# LED.net
KiCad netlist of a schematic drawn in EAGLE
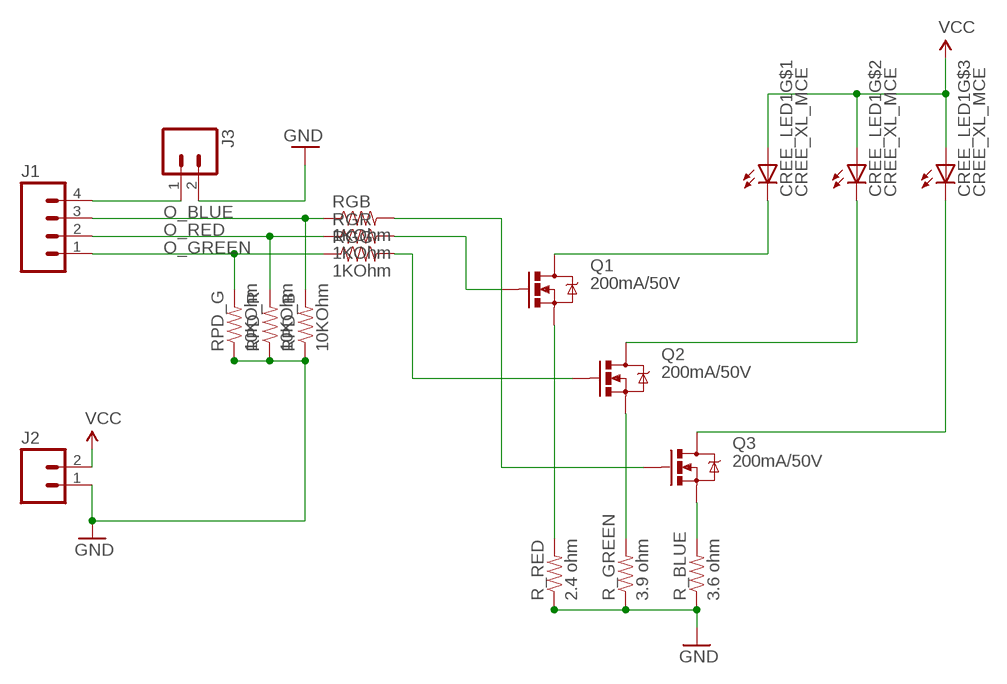
[diagram p0: schematic, sheet 1]

(export (version "E")
  (design (tool "Eeschema 10.0.6"))
  (components
    (comp (ref "CREE_LED1")
      (value "CREE_XL_MCE")
      (footprint "eagle-import:CREE_XL_MCE")
      (libsource (lib "eagle-import") (part "CREE_XL_MCE"))
    )
    (comp (ref "J1")
      (value "M04NO_SILK_ALL_ROUND")
      (footprint "eagle-import:1X04_NO_SILK_ALL_ROUND")
      (libsource (lib "eagle-import") (part "M04NO_SILK_ALL_ROUND"))
    )
    (comp (ref "J2")
      (value "M021X02_NO_SILK")
      (footprint "eagle-import:1X02_NO_SILK")
      (libsource (lib "eagle-import") (part "M021X02_NO_SILK"))
    )
    (comp (ref "J3")
      (value "M021X02_NO_SILK")
      (footprint "eagle-import:1X02_NO_SILK")
      (libsource (lib "eagle-import") (part "M021X02_NO_SILK"))
    )
    (comp (ref "Q1")
      (value "200mA/50V")
      (footprint "eagle-import:SOT23-3")
      (libsource (lib "eagle-import") (part "MOSFET-NCHANNELBSS138"))
    )
    (comp (ref "Q2")
      (value "200mA/50V")
      (footprint "eagle-import:SOT23-3")
      (libsource (lib "eagle-import") (part "MOSFET-NCHANNELBSS138"))
    )
    (comp (ref "Q3")
      (value "200mA/50V")
      (footprint "eagle-import:SOT23-3")
      (libsource (lib "eagle-import") (part "MOSFET-NCHANNELBSS138"))
    )
    (comp (ref "RGB")
      (value "1KOhm")
      (footprint "eagle-import:0805")
      (libsource (lib "eagle-import") (part "RESISTOR0805-RES"))
    )
    (comp (ref "RGG")
      (value "1KOhm")
      (footprint "eagle-import:0805")
      (libsource (lib "eagle-import") (part "RESISTOR0805-RES"))
    )
    (comp (ref "RGR")
      (value "1KOhm")
      (footprint "eagle-import:0805")
      (libsource (lib "eagle-import") (part "RESISTOR0805-RES"))
    )
    (comp (ref "RPD_B")
      (value "10KOhm")
      (footprint "eagle-import:0805")
      (libsource (lib "eagle-import") (part "RESISTOR0805-RES"))
    )
    (comp (ref "RPD_G")
      (value "10KOhm")
      (footprint "eagle-import:0805")
      (libsource (lib "eagle-import") (part "RESISTOR0805-RES"))
    )
    (comp (ref "RPD_R")
      (value "10KOhm")
      (footprint "eagle-import:0805")
      (libsource (lib "eagle-import") (part "RESISTOR0805-RES"))
    )
    (comp (ref "R_BLUE")
      (value "3.6 ohm")
      (footprint "eagle-import:0805")
      (libsource (lib "eagle-import") (part "RESISTOR0805-RES"))
    )
    (comp (ref "R_GREEN")
      (value "3.9 ohm")
      (footprint "eagle-import:0805")
      (libsource (lib "eagle-import") (part "RESISTOR0805-RES"))
    )
    (comp (ref "R_RED")
      (value "2.4 ohm")
      (footprint "eagle-import:0805")
      (libsource (lib "eagle-import") (part "RESISTOR0805-RES"))
    )
  )
  (nets
    (net (code "1") (name "/O_BLUE") (class "Default")
      (node (ref "J1") (pin "3") (pinfunction "3_3") (pintype "passive"))
      (node (ref "RGB") (pin "1") (pinfunction "1_1") (pintype "passive"))
      (node (ref "RPD_B") (pin "2") (pinfunction "2_2") (pintype "passive"))
    )
    (net (code "2") (name "/O_GREEN") (class "Default")
      (node (ref "J1") (pin "1") (pinfunction "1_1") (pintype "passive"))
      (node (ref "RGG") (pin "1") (pinfunction "1_1") (pintype "passive"))
      (node (ref "RPD_G") (pin "2") (pinfunction "2_2") (pintype "passive"))
    )
    (net (code "3") (name "/O_RED") (class "Default")
      (node (ref "J1") (pin "2") (pinfunction "2_2") (pintype "passive"))
      (node (ref "RGR") (pin "1") (pinfunction "1_1") (pintype "passive"))
      (node (ref "RPD_R") (pin "2") (pinfunction "2_2") (pintype "passive"))
    )
    (net (code "4") (name "GND") (class "Default")
      (node (ref "J2") (pin "1") (pinfunction "1_1") (pintype "passive"))
      (node (ref "J3") (pin "2") (pinfunction "2_2") (pintype "passive"))
      (node (ref "RPD_B") (pin "1") (pinfunction "1_1") (pintype "passive"))
      (node (ref "RPD_G") (pin "1") (pinfunction "1_1") (pintype "passive"))
      (node (ref "RPD_R") (pin "1") (pinfunction "1_1") (pintype "passive"))
      (node (ref "R_BLUE") (pin "1") (pinfunction "1_1") (pintype "passive"))
      (node (ref "R_GREEN") (pin "1") (pinfunction "1_1") (pintype "passive"))
      (node (ref "R_RED") (pin "1") (pinfunction "1_1") (pintype "passive"))
    )
    (net (code "5") (name "Net-(CREE_LED1A-C)") (class "Default")
      (node (ref "CREE_LED1") (pin "8") (pinfunction "C_8") (pintype "passive"))
      (node (ref "Q1") (pin "3") (pinfunction "D_3") (pintype "passive"))
    )
    (net (code "6") (name "Net-(CREE_LED1B-C)") (class "Default")
      (node (ref "CREE_LED1") (pin "7") (pinfunction "C_7") (pintype "passive"))
      (node (ref "Q2") (pin "3") (pinfunction "D_3") (pintype "passive"))
    )
    (net (code "7") (name "Net-(CREE_LED1C-C)") (class "Default")
      (node (ref "CREE_LED1") (pin "6") (pinfunction "C_6") (pintype "passive"))
      (node (ref "Q3") (pin "3") (pinfunction "D_3") (pintype "passive"))
    )
    (net (code "8") (name "Net-(J1-Pad4)") (class "Default")
      (node (ref "J1") (pin "4") (pinfunction "4_4") (pintype "passive"))
      (node (ref "J3") (pin "1") (pinfunction "1_1") (pintype "passive"))
    )
    (net (code "9") (name "Net-(Q1-G)") (class "Default")
      (node (ref "Q1") (pin "1") (pinfunction "G_1") (pintype "passive"))
      (node (ref "RGR") (pin "2") (pinfunction "2_2") (pintype "passive"))
    )
    (net (code "10") (name "Net-(Q1-S)") (class "Default")
      (node (ref "Q1") (pin "2") (pinfunction "S_2") (pintype "passive"))
      (node (ref "R_RED") (pin "2") (pinfunction "2_2") (pintype "passive"))
    )
    (net (code "11") (name "Net-(Q2-G)") (class "Default")
      (node (ref "Q2") (pin "1") (pinfunction "G_1") (pintype "passive"))
      (node (ref "RGG") (pin "2") (pinfunction "2_2") (pintype "passive"))
    )
    (net (code "12") (name "Net-(Q2-S)") (class "Default")
      (node (ref "Q2") (pin "2") (pinfunction "S_2") (pintype "passive"))
      (node (ref "R_GREEN") (pin "2") (pinfunction "2_2") (pintype "passive"))
    )
    (net (code "13") (name "Net-(Q3-G)") (class "Default")
      (node (ref "Q3") (pin "1") (pinfunction "G_1") (pintype "passive"))
      (node (ref "RGB") (pin "2") (pinfunction "2_2") (pintype "passive"))
    )
    (net (code "14") (name "Net-(Q3-S)") (class "Default")
      (node (ref "Q3") (pin "2") (pinfunction "S_2") (pintype "passive"))
      (node (ref "R_BLUE") (pin "2") (pinfunction "2_2") (pintype "passive"))
    )
    (net (code "15") (name "VCC") (class "Default")
      (node (ref "CREE_LED1") (pin "1") (pinfunction "A_1") (pintype "passive"))
      (node (ref "CREE_LED1") (pin "2") (pinfunction "A_2") (pintype "passive"))
      (node (ref "CREE_LED1") (pin "3") (pinfunction "A_3") (pintype "passive"))
      (node (ref "J2") (pin "2") (pinfunction "2_2") (pintype "passive"))
    )
  )
)
